# isoSPI_Interface.net
KiCad netlist of a schematic drawn in Altium Designer
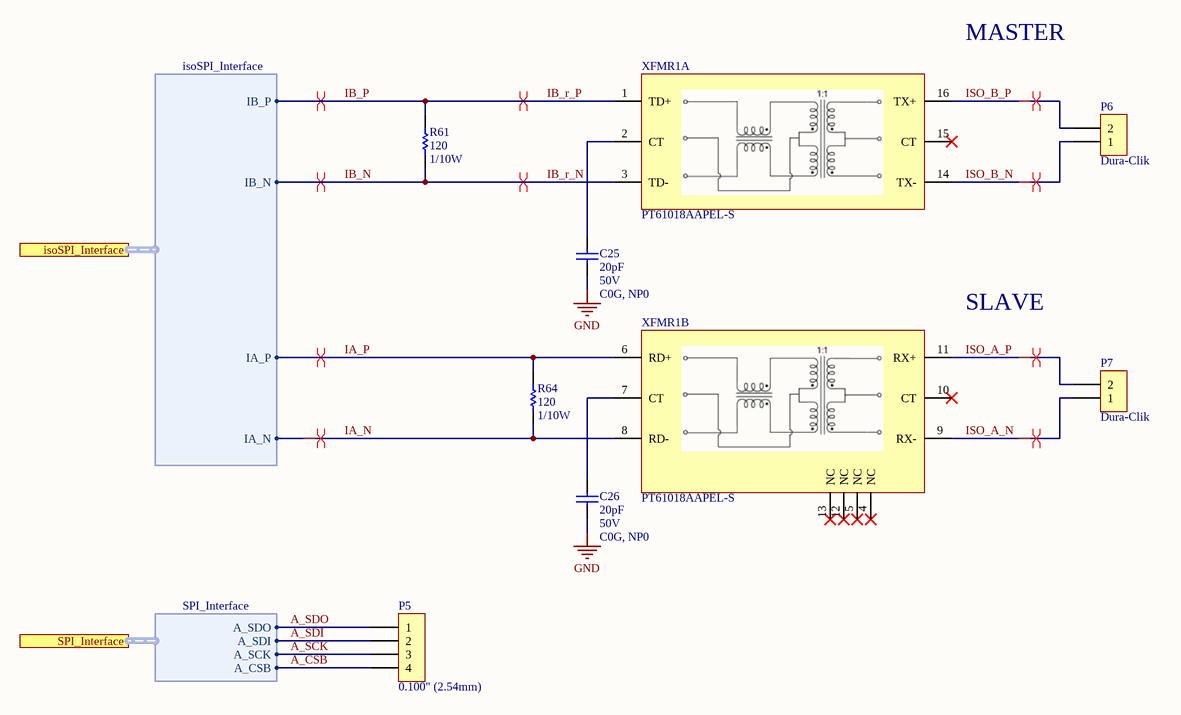
[diagram p0: isoSPI_Interface.SchDoc]

(export (version "E")
  (design (tool "Eeschema 10.0.6"))
  (components
    (comp (ref "C25")
      (value "CAP CER 20PF 50V ±5% C0G/NP0 0603")
      (footprint "CAP, 0603")
      (description "20pF ±5% 50V Ceramic Capacitor C0G, NP0 0603 (1608 Metric)")
      (fields
        (field (name "TOLERANCE") "±5%")
        (field (name "CAPACITANCE") "20pF")
        (field (name "VOLTAGE") "50V")
        (field (name "TEMPERATURE COEFFICIENT") "C0G, NP0")
      )
      (libsource (lib "Schematic Diagrams") (part "CAP CER 20PF 50V ±5% C0G/NP0 0603"))
    )
    (comp (ref "C26")
      (value "CAP CER 20PF 50V ±5% C0G/NP0 0603")
      (footprint "CAP, 0603")
      (description "20pF ±5% 50V Ceramic Capacitor C0G, NP0 0603 (1608 Metric)")
      (fields
        (field (name "TOLERANCE") "±5%")
        (field (name "CAPACITANCE") "20pF")
        (field (name "VOLTAGE") "50V")
        (field (name "TEMPERATURE COEFFICIENT") "C0G, NP0")
      )
      (libsource (lib "Schematic Diagrams") (part "CAP CER 20PF 50V ±5% C0G/NP0 0603"))
    )
    (comp (ref "P5")
      (value "CONN 4POS HEADR MALE 0.1\"")
      (footprint "CONN 4POS 0.100\"")
      (description "4 Positions Header Connector 0.100\" (2.54mm) Through Hole Gold")
      (fields (field (name "VOLTAGE") "250V") (field (name "PITCH - MATING") "0.100\" (2.54mm)"))
      (libsource (lib "Schematic Diagrams") (part "CONN 4POS HEADR MALE 0.1{dblquote}"))
    )
    (comp (ref "P6")
      (value "Dura-Clik")
      (footprint "CONN, 2POS Dura-Click Vertical")
      (description "2 Positions Header, Shrouded Connector 0.079\" (2.00mm) Surface Mount, Vertical Tin")
      (fields
        (field (name "MANUFACTURER") "Molex, LLC")
        (field (name "MANUFACTURER PART NUMBER") "5600200220")
      )
      (libsource (lib "Schematic Diagrams") (part "CONN 2POS DURA-CLIK 0.079{dblquote} VERT"))
    )
    (comp (ref "P7")
      (value "Dura-Clik")
      (footprint "CONN, 2POS Dura-Click Vertical")
      (description "2 Positions Header, Shrouded Connector 0.079\" (2.00mm) Surface Mount, Vertical Tin")
      (fields
        (field (name "MANUFACTURER") "Molex, LLC")
        (field (name "MANUFACTURER PART NUMBER") "5600200220")
      )
      (libsource (lib "Schematic Diagrams") (part "CONN 2POS DURA-CLIK 0.079{dblquote} VERT"))
    )
    (comp (ref "R61")
      (value "RES 120 OHM 1% 1/10W 0603")
      (footprint "RES, 0603")
      (description "RES SMD 120 OHM 1% 1/10W 0603")
      (fields
        (field (name "TOLERANCE") "±1%")
        (field (name "RESISTANCE") "120")
        (field (name "POWER") "1/10W")
      )
      (libsource (lib "Schematic Diagrams") (part "RES 120 OHM 1% 1/10W 0603"))
    )
    (comp (ref "R64")
      (value "RES 120 OHM 1% 1/10W 0603")
      (footprint "RES, 0603")
      (description "RES SMD 120 OHM 1% 1/10W 0603")
      (fields
        (field (name "TOLERANCE") "±1%")
        (field (name "RESISTANCE") "120")
        (field (name "POWER") "1/10W")
      )
      (libsource (lib "Schematic Diagrams") (part "RES 120 OHM 1% 1/10W 0603"))
    )
    (comp (ref "XFMR1")
      (value "IC PULSE XFMR 1CT:1CT 350UH SMD")
      (footprint "IC, PULSE XFMR 1CT:1CT 350UH SMD")
      (description "PULSE XFMR 1CT:1CT 350UH SMD")
      (fields (field (name "MANUFACTURER") "Bourns Inc.") (field (name "MFG_PN") "PT61018AAPEL-S"))
      (libsource (lib "Schematic Diagrams") (part "IC PULSE XFMR 1CT{colon}1CT 350UH SMD"))
    )
  )
  (nets
    (net (code "3") (name "/A_CSB") (class "Default")
      (node (ref "P5") (pin "4") (pinfunction "4_4") (pintype "passive"))
    )
    (net (code "4") (name "/A_SCK") (class "Default")
      (node (ref "P5") (pin "3") (pinfunction "3_3") (pintype "passive"))
    )
    (net (code "5") (name "/A_SDI") (class "Default")
      (node (ref "P5") (pin "2") (pinfunction "2_2") (pintype "passive"))
    )
    (net (code "6") (name "/A_SDO") (class "Default")
      (node (ref "P5") (pin "1") (pinfunction "1_1") (pintype "passive"))
    )
    (net (code "7") (name "/IA_N") (class "Default")
      (node (ref "R64") (pin "2") (pinfunction "2_2") (pintype "passive"))
      (node (ref "XFMR1") (pin "8") (pinfunction "RD-_8") (pintype "passive"))
    )
    (net (code "8") (name "/IA_P") (class "Default")
      (node (ref "R64") (pin "1") (pinfunction "1_1") (pintype "passive"))
      (node (ref "XFMR1") (pin "6") (pinfunction "RD+_6") (pintype "passive"))
    )
    (net (code "9") (name "/IB_N") (class "Default")
      (node (ref "R61") (pin "2") (pinfunction "2_2") (pintype "passive"))
      (node (ref "XFMR1") (pin "3") (pinfunction "TD-_3") (pintype "passive"))
    )
    (net (code "10") (name "/IB_P") (class "Default")
      (node (ref "R61") (pin "1") (pinfunction "1_1") (pintype "passive"))
      (node (ref "XFMR1") (pin "1") (pinfunction "TD+_1") (pintype "passive"))
    )
    (net (code "11") (name "/ISO_A_N") (class "Default")
      (node (ref "P7") (pin "1") (pinfunction "1_1") (pintype "passive"))
      (node (ref "XFMR1") (pin "9") (pinfunction "RX-_9") (pintype "passive"))
    )
    (net (code "12") (name "/ISO_A_P") (class "Default")
      (node (ref "P7") (pin "2") (pinfunction "2_2") (pintype "passive"))
      (node (ref "XFMR1") (pin "11") (pinfunction "RX+_11") (pintype "passive"))
    )
    (net (code "13") (name "/ISO_B_N") (class "Default")
      (node (ref "P6") (pin "1") (pinfunction "1_1") (pintype "passive"))
      (node (ref "XFMR1") (pin "14") (pinfunction "TX-_14") (pintype "passive"))
    )
    (net (code "14") (name "/ISO_B_P") (class "Default")
      (node (ref "P6") (pin "2") (pinfunction "2_2") (pintype "passive"))
      (node (ref "XFMR1") (pin "16") (pinfunction "TX+_16") (pintype "passive"))
    )
    (net (code "17") (name "GND") (class "Default")
      (node (ref "C25") (pin "2") (pinfunction "2_2") (pintype "passive"))
      (node (ref "C26") (pin "2") (pinfunction "2_2") (pintype "passive"))
    )
    (net (code "18") (name "Net-(C25-Pad1)") (class "Default")
      (node (ref "C25") (pin "1") (pinfunction "1_1") (pintype "passive"))
      (node (ref "XFMR1") (pin "2") (pinfunction "CT_2") (pintype "passive"))
    )
    (net (code "19") (name "Net-(C26-Pad1)") (class "Default")
      (node (ref "C26") (pin "1") (pinfunction "1_1") (pintype "passive"))
      (node (ref "XFMR1") (pin "7") (pinfunction "CT_7") (pintype "passive"))
    )
    (net (code "20") (name "unconnected-(XFMR1A-CT-Pad15)") (class "Default")
      (node (ref "XFMR1") (pin "15") (pinfunction "CT_15") (pintype "passive+no_connect"))
    )
    (net (code "21") (name "unconnected-(XFMR1B-CT-Pad10)") (class "Default")
      (node (ref "XFMR1") (pin "10") (pinfunction "CT_10") (pintype "passive+no_connect"))
    )
    (net (code "22") (name "unconnected-(XFMR1B-NC-Pad4)") (class "Default")
      (node (ref "XFMR1") (pin "4") (pinfunction "NC_4") (pintype "passive+no_connect"))
    )
    (net (code "23") (name "unconnected-(XFMR1B-NC-Pad5)") (class "Default")
      (node (ref "XFMR1") (pin "5") (pinfunction "NC_5") (pintype "passive+no_connect"))
    )
    (net (code "24") (name "unconnected-(XFMR1B-NC-Pad12)") (class "Default")
      (node (ref "XFMR1") (pin "12") (pinfunction "NC_12") (pintype "passive+no_connect"))
    )
    (net (code "25") (name "unconnected-(XFMR1B-NC-Pad13)") (class "Default")
      (node (ref "XFMR1") (pin "13") (pinfunction "NC_13") (pintype "passive+no_connect"))
    )
  )
)
